# blitzbox.net
KiCad netlist of a schematic drawn in EAGLE
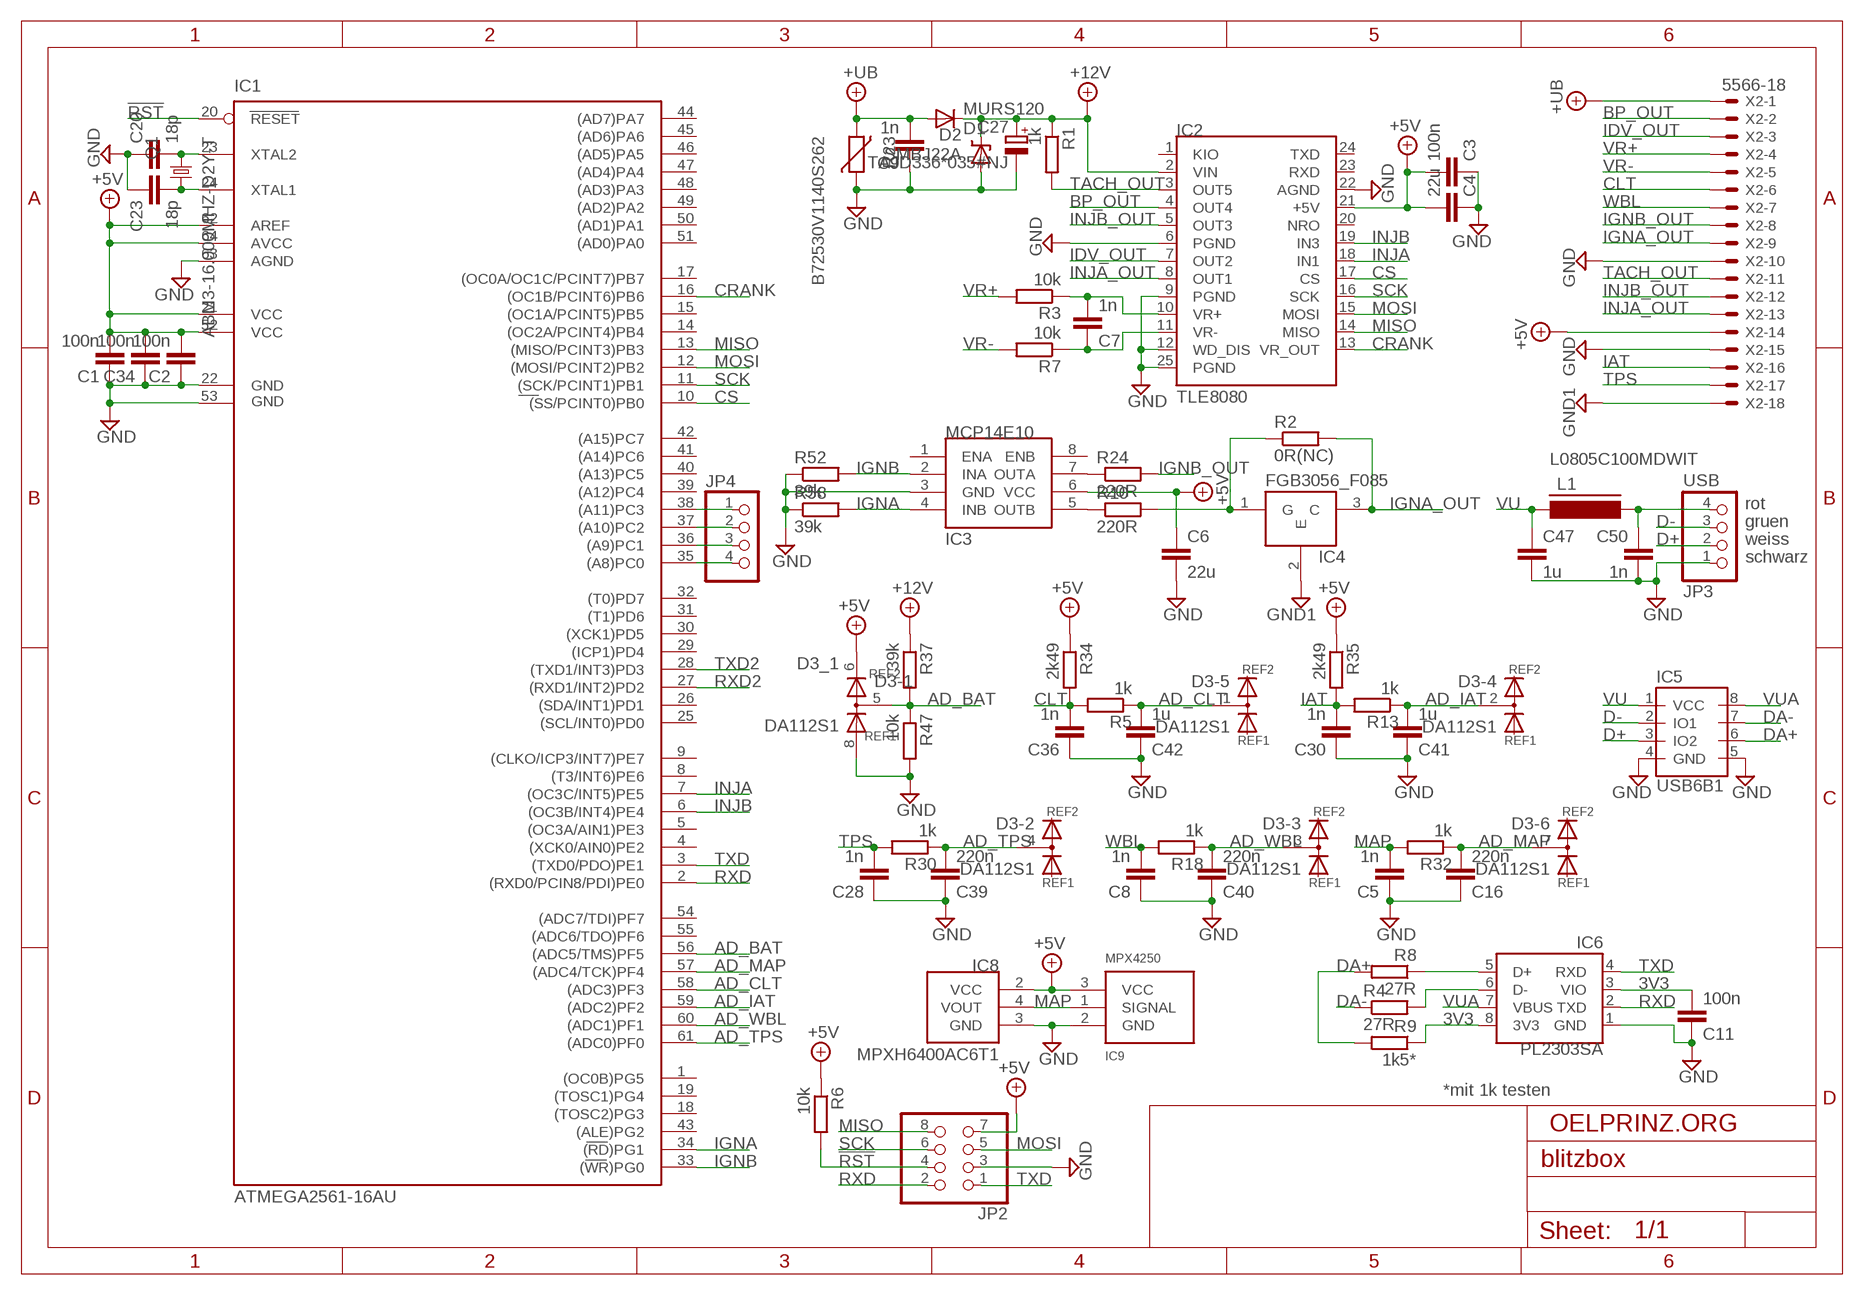
[diagram p0: schematic, sheet 1]

(export (version "E")
  (design (tool "Eeschema 10.0.6"))
  (components
    (comp (ref "C1")
      (value "100n")
      (footprint "eagle-import:C0805")
      (libsource (lib "eagle-import") (part "C-EUC0805"))
    )
    (comp (ref "C2")
      (value "100n")
      (footprint "eagle-import:C0805")
      (libsource (lib "eagle-import") (part "C-EUC0805"))
    )
    (comp (ref "C3")
      (value "100n")
      (footprint "eagle-import:C0805")
      (libsource (lib "eagle-import") (part "C-EUC0805"))
    )
    (comp (ref "C4")
      (value "22u")
      (footprint "eagle-import:C1210")
      (libsource (lib "eagle-import") (part "C-EUC1210"))
    )
    (comp (ref "C5")
      (value "1n")
      (footprint "eagle-import:C0805")
      (libsource (lib "eagle-import") (part "C-EUC0805"))
    )
    (comp (ref "C6")
      (value "22u")
      (footprint "eagle-import:C1206")
      (libsource (lib "eagle-import") (part "C-EUC1206"))
    )
    (comp (ref "C7")
      (value "1n")
      (footprint "eagle-import:C0805")
      (libsource (lib "eagle-import") (part "C-EUC0805"))
    )
    (comp (ref "C8")
      (value "1n")
      (footprint "eagle-import:C0805")
      (libsource (lib "eagle-import") (part "C-EUC0805"))
    )
    (comp (ref "C9")
      (value "1n")
      (footprint "eagle-import:C0805")
      (libsource (lib "eagle-import") (part "C-EUC0805"))
    )
    (comp (ref "C11")
      (value "100n")
      (footprint "eagle-import:C0805")
      (libsource (lib "eagle-import") (part "C-EUC0805"))
    )
    (comp (ref "C16")
      (value "220n")
      (footprint "eagle-import:C0805")
      (libsource (lib "eagle-import") (part "C-EUC0805"))
    )
    (comp (ref "C20")
      (value "18p")
      (footprint "eagle-import:C0805")
      (libsource (lib "eagle-import") (part "C-EUC0805"))
    )
    (comp (ref "C23")
      (value "18p")
      (footprint "eagle-import:C0805")
      (libsource (lib "eagle-import") (part "C-EUC0805"))
    )
    (comp (ref "C27")
      (value "TAJD336*035#NJ")
      (footprint "eagle-import:SMC_D")
      (libsource (lib "eagle-import") (part "CPOL-EUSMCD"))
    )
    (comp (ref "C28")
      (value "1n")
      (footprint "eagle-import:C0805")
      (libsource (lib "eagle-import") (part "C-EUC0805"))
    )
    (comp (ref "C30")
      (value "1n")
      (footprint "eagle-import:C0805")
      (libsource (lib "eagle-import") (part "C-EUC0805"))
    )
    (comp (ref "C34")
      (value "100n")
      (footprint "eagle-import:C0805")
      (libsource (lib "eagle-import") (part "C-EUC0805"))
    )
    (comp (ref "C36")
      (value "1n")
      (footprint "eagle-import:C0805")
      (libsource (lib "eagle-import") (part "C-EUC0805"))
    )
    (comp (ref "C39")
      (value "220n")
      (footprint "eagle-import:C0805")
      (libsource (lib "eagle-import") (part "C-EUC0805"))
    )
    (comp (ref "C40")
      (value "220n")
      (footprint "eagle-import:C0805")
      (libsource (lib "eagle-import") (part "C-EUC0805"))
    )
    (comp (ref "C41")
      (value "1u")
      (footprint "eagle-import:C0805")
      (libsource (lib "eagle-import") (part "C-EUC0805"))
    )
    (comp (ref "C42")
      (value "1u")
      (footprint "eagle-import:C0805")
      (libsource (lib "eagle-import") (part "C-EUC0805"))
    )
    (comp (ref "C47")
      (value "1u")
      (footprint "eagle-import:C0805")
      (libsource (lib "eagle-import") (part "C-EUC0805"))
    )
    (comp (ref "C50")
      (value "1n")
      (footprint "eagle-import:C0805")
      (libsource (lib "eagle-import") (part "C-EUC0805"))
    )
    (comp (ref "D1")
      (value "MURS120")
      (footprint "eagle-import:MURS120")
      (libsource (lib "eagle-import") (part "MURS120"))
    )
    (comp (ref "D2")
      (value "SMBJ22A")
      (footprint "eagle-import:SMBJ")
      (libsource (lib "eagle-import") (part "SUPPRESSOR-SMBJ"))
    )
    (comp (ref "D3")
      (value "DA112S1")
      (footprint "eagle-import:SO08")
      (fields (field (name "MF") "Arrow Electronics"))
      (libsource (lib "eagle-import") (part "DA112S1"))
    )
    (comp (ref "IC1")
      (value "ATMEGA2561-16AU")
      (footprint "eagle-import:TQFP64")
      (libsource (lib "eagle-import") (part "ATMEGA2561AU-16"))
    )
    (comp (ref "IC2")
      (value "TLE8080")
      (footprint "eagle-import:TLE8080")
      (libsource (lib "eagle-import") (part "TLE8080"))
    )
    (comp (ref "IC3")
      (value "MCP14E10")
      (footprint "eagle-import:SO-08")
      (libsource (lib "eagle-import") (part "MCP14E10"))
    )
    (comp (ref "IC4")
      (value "FGB3056_F085")
      (footprint "eagle-import:TO263")
      (libsource (lib "eagle-import") (part "FGB3056_F085"))
    )
    (comp (ref "IC5")
      (value "USB6B1")
      (footprint "eagle-import:SO08")
      (libsource (lib "eagle-import") (part "USB6B1"))
    )
    (comp (ref "IC6")
      (value "PL2303SA")
      (footprint "eagle-import:SO-08")
      (libsource (lib "eagle-import") (part "PL2303SA"))
    )
    (comp (ref "IC8")
      (value "MPXH6400AC6T1")
      (footprint "eagle-import:MPXH6400")
      (libsource (lib "eagle-import") (part "MPXH6400"))
    )
    (comp (ref "IC9")
      (value "MPX4250")
      (footprint "eagle-import:MPX4250")
      (libsource (lib "eagle-import") (part "MPX4250"))
    )
    (comp (ref "JP2")
      (value "PINHD-2X4")
      (footprint "eagle-import:2X04")
      (libsource (lib "eagle-import") (part "PINHD-2X4"))
    )
    (comp (ref "JP3")
      (value "USB")
      (footprint "eagle-import:1X04")
      (libsource (lib "eagle-import") (part "PINHD-1X4"))
    )
    (comp (ref "JP4")
      (value "PINHD-1X4")
      (footprint "eagle-import:1X04")
      (libsource (lib "eagle-import") (part "PINHD-1X4"))
    )
    (comp (ref "L1")
      (value "L0805C100MDWIT")
      (footprint "eagle-import:FB805")
      (libsource (lib "eagle-import") (part "FERRITE_BEAD805"))
    )
    (comp (ref "Q1")
      (value "ABM3-16.000MHZ-D2Y-T")
      (footprint "eagle-import:ABM3")
      (libsource (lib "eagle-import") (part "ABM3-8.000MHZ-D2Y-T"))
    )
    (comp (ref "R1")
      (value "1k")
      (footprint "eagle-import:R0805")
      (libsource (lib "eagle-import") (part "R-EU_R0805"))
    )
    (comp (ref "R2")
      (value "0R(NC)")
      (footprint "eagle-import:R0805")
      (libsource (lib "eagle-import") (part "R-EU_R0805"))
    )
    (comp (ref "R3")
      (value "10k")
      (footprint "eagle-import:R0805")
      (libsource (lib "eagle-import") (part "R-EU_R0805"))
    )
    (comp (ref "R4")
      (value "27R")
      (footprint "eagle-import:R0805")
      (libsource (lib "eagle-import") (part "R-EU_R0805"))
    )
    (comp (ref "R5")
      (value "1k")
      (footprint "eagle-import:R0805")
      (libsource (lib "eagle-import") (part "R-EU_R0805"))
    )
    (comp (ref "R6")
      (value "10k")
      (footprint "eagle-import:R0805")
      (libsource (lib "eagle-import") (part "R-EU_R0805"))
    )
    (comp (ref "R7")
      (value "10k")
      (footprint "eagle-import:R0805")
      (libsource (lib "eagle-import") (part "R-EU_R0805"))
    )
    (comp (ref "R8")
      (value "27R")
      (footprint "eagle-import:R0805")
      (libsource (lib "eagle-import") (part "R-EU_R0805"))
    )
    (comp (ref "R9")
      (value "1k5*")
      (footprint "eagle-import:R0805")
      (libsource (lib "eagle-import") (part "R-EU_R0805"))
    )
    (comp (ref "R10")
      (value "220R")
      (footprint "eagle-import:R0805")
      (libsource (lib "eagle-import") (part "R-EU_R0805"))
    )
    (comp (ref "R13")
      (value "1k")
      (footprint "eagle-import:R0805")
      (libsource (lib "eagle-import") (part "R-EU_R0805"))
    )
    (comp (ref "R18")
      (value "1k")
      (footprint "eagle-import:R0805")
      (libsource (lib "eagle-import") (part "R-EU_R0805"))
    )
    (comp (ref "R23")
      (value "B72530V1140S262")
      (footprint "eagle-import:CT_CN1210")
      (libsource (lib "eagle-import") (part "VARISTORCN1210"))
    )
    (comp (ref "R24")
      (value "220R")
      (footprint "eagle-import:R0805")
      (libsource (lib "eagle-import") (part "R-EU_R0805"))
    )
    (comp (ref "R30")
      (value "1k")
      (footprint "eagle-import:R0805")
      (libsource (lib "eagle-import") (part "R-EU_R0805"))
    )
    (comp (ref "R32")
      (value "1k")
      (footprint "eagle-import:R0805")
      (libsource (lib "eagle-import") (part "R-EU_R0805"))
    )
    (comp (ref "R34")
      (value "2k49")
      (footprint "eagle-import:R0805")
      (libsource (lib "eagle-import") (part "R-EU_R0805"))
    )
    (comp (ref "R35")
      (value "2k49")
      (footprint "eagle-import:R0805")
      (libsource (lib "eagle-import") (part "R-EU_R0805"))
    )
    (comp (ref "R37")
      (value "39k")
      (footprint "eagle-import:R0805")
      (libsource (lib "eagle-import") (part "R-EU_R0805"))
    )
    (comp (ref "R47")
      (value "10k")
      (footprint "eagle-import:R0805")
      (libsource (lib "eagle-import") (part "R-EU_R0805"))
    )
    (comp (ref "R52")
      (value "39k")
      (footprint "eagle-import:R0805")
      (libsource (lib "eagle-import") (part "R-EU_R0805"))
    )
    (comp (ref "R58")
      (value "39k")
      (footprint "eagle-import:R0805")
      (libsource (lib "eagle-import") (part "R-EU_R0805"))
    )
    (comp (ref "X2")
      (value "5566-18")
      (footprint "eagle-import:5566-18")
      (libsource (lib "eagle-import") (part "5566-18"))
    )
  )
  (nets
    (net (code "1") (name "+5V") (class "Default")
      (node (ref "C1") (pin "2") (pinfunction "2_2") (pintype "passive"))
      (node (ref "C2") (pin "2") (pinfunction "2_2") (pintype "passive"))
      (node (ref "C3") (pin "2") (pinfunction "2_2") (pintype "passive"))
      (node (ref "C34") (pin "2") (pinfunction "2_2") (pintype "passive"))
      (node (ref "C4") (pin "2") (pinfunction "2_2") (pintype "passive"))
      (node (ref "C6") (pin "1") (pinfunction "1_1") (pintype "passive"))
      (node (ref "D3") (pin "6") (pinfunction "REF2_6") (pintype "passive"))
      (node (ref "IC1") (pin "21") (pinfunction "VCC_21") (pintype "power_in"))
      (node (ref "IC1") (pin "52") (pinfunction "VCC1_52") (pintype "power_in"))
      (node (ref "IC1") (pin "62") (pinfunction "AREF_62") (pintype "bidirectional"))
      (node (ref "IC1") (pin "64") (pinfunction "AVCC_64") (pintype "power_in"))
      (node (ref "IC2") (pin "21") (pinfunction "+5V_21") (pintype "bidirectional"))
      (node (ref "IC3") (pin "6") (pinfunction "VCC_6") (pintype "bidirectional"))
      (node (ref "IC8") (pin "2") (pinfunction "VCC_2") (pintype "bidirectional"))
      (node (ref "IC9") (pin "3") (pinfunction "VCC_3") (pintype "bidirectional"))
      (node (ref "JP2") (pin "7") (pinfunction "7_7") (pintype "passive"))
      (node (ref "R34") (pin "1") (pinfunction "1_1") (pintype "passive"))
      (node (ref "R35") (pin "1") (pinfunction "1_1") (pintype "passive"))
      (node (ref "R6") (pin "1") (pinfunction "1_1") (pintype "passive"))
      (node (ref "X2") (pin "14") (pinfunction "S_14") (pintype "passive"))
    )
    (net (code "2") (name "+12V") (class "Default")
      (node (ref "C27") (pin "+") (pinfunction "+_+") (pintype "passive"))
      (node (ref "D1") (pin "2") (pinfunction "C_2") (pintype "passive"))
      (node (ref "D2") (pin "C") (pinfunction "C_C") (pintype "passive"))
      (node (ref "IC2") (pin "2") (pinfunction "VIN_2") (pintype "bidirectional"))
      (node (ref "R1") (pin "1") (pinfunction "1_1") (pintype "passive"))
      (node (ref "R37") (pin "1") (pinfunction "1_1") (pintype "passive"))
    )
    (net (code "3") (name "+UB") (class "Default")
      (node (ref "C9") (pin "2") (pinfunction "2_2") (pintype "passive"))
      (node (ref "D1") (pin "1") (pinfunction "A_1") (pintype "passive"))
      (node (ref "R23") (pin "2") (pinfunction "2_2") (pintype "passive"))
      (node (ref "X2") (pin "1") (pinfunction "S_1") (pintype "passive"))
    )
    (net (code "4") (name "/3V3") (class "Default")
      (node (ref "C11") (pin "2") (pinfunction "2_2") (pintype "passive"))
      (node (ref "IC6") (pin "3") (pinfunction "VIO_3") (pintype "bidirectional"))
      (node (ref "IC6") (pin "8") (pinfunction "3V3_8") (pintype "bidirectional"))
      (node (ref "R9") (pin "1") (pinfunction "1_1") (pintype "passive"))
    )
    (net (code "5") (name "/AD_BAT") (class "Default")
      (node (ref "D3") (pin "5") (pinfunction "K_5") (pintype "passive"))
      (node (ref "IC1") (pin "56") (pinfunction "(ADC5/TMS)PF5_56") (pintype "bidirectional"))
      (node (ref "R37") (pin "2") (pinfunction "2_2") (pintype "passive"))
      (node (ref "R47") (pin "1") (pinfunction "1_1") (pintype "passive"))
    )
    (net (code "6") (name "/AD_CLT") (class "Default")
      (node (ref "C42") (pin "2") (pinfunction "2_2") (pintype "passive"))
      (node (ref "D3") (pin "1") (pinfunction "K_1") (pintype "passive"))
      (node (ref "IC1") (pin "58") (pinfunction "(ADC3)PF3_58") (pintype "bidirectional"))
      (node (ref "R5") (pin "1") (pinfunction "1_1") (pintype "passive"))
    )
    (net (code "7") (name "/AD_IAT") (class "Default")
      (node (ref "C41") (pin "2") (pinfunction "2_2") (pintype "passive"))
      (node (ref "D3") (pin "2") (pinfunction "K_2") (pintype "passive"))
      (node (ref "IC1") (pin "59") (pinfunction "(ADC2)PF2_59") (pintype "bidirectional"))
      (node (ref "R13") (pin "1") (pinfunction "1_1") (pintype "passive"))
    )
    (net (code "8") (name "/AD_MAP") (class "Default")
      (node (ref "C16") (pin "2") (pinfunction "2_2") (pintype "passive"))
      (node (ref "D3") (pin "7") (pinfunction "K_7") (pintype "passive"))
      (node (ref "IC1") (pin "57") (pinfunction "(ADC4/TCK)PF4_57") (pintype "bidirectional"))
      (node (ref "R32") (pin "1") (pinfunction "1_1") (pintype "passive"))
    )
    (net (code "9") (name "/AD_TPS") (class "Default")
      (node (ref "C39") (pin "2") (pinfunction "2_2") (pintype "passive"))
      (node (ref "D3") (pin "4") (pinfunction "K_4") (pintype "passive"))
      (node (ref "IC1") (pin "61") (pinfunction "(ADC0)PF0_61") (pintype "bidirectional"))
      (node (ref "R30") (pin "1") (pinfunction "1_1") (pintype "passive"))
    )
    (net (code "10") (name "/AD_WBL") (class "Default")
      (node (ref "C40") (pin "2") (pinfunction "2_2") (pintype "passive"))
      (node (ref "D3") (pin "3") (pinfunction "K_3") (pintype "passive"))
      (node (ref "IC1") (pin "60") (pinfunction "(ADC1)PF1_60") (pintype "bidirectional"))
      (node (ref "R18") (pin "1") (pinfunction "1_1") (pintype "passive"))
    )
    (net (code "11") (name "/BP_OUT") (class "Default")
      (node (ref "IC2") (pin "4") (pinfunction "OUT4_4") (pintype "bidirectional"))
      (node (ref "X2") (pin "2") (pinfunction "S_2") (pintype "passive"))
    )
    (net (code "12") (name "/CLT") (class "Default")
      (node (ref "C36") (pin "2") (pinfunction "2_2") (pintype "passive"))
      (node (ref "R34") (pin "2") (pinfunction "2_2") (pintype "passive"))
      (node (ref "R5") (pin "2") (pinfunction "2_2") (pintype "passive"))
      (node (ref "X2") (pin "6") (pinfunction "S_6") (pintype "passive"))
    )
    (net (code "13") (name "/CRANK") (class "Default")
      (node (ref "IC1") (pin "16") (pinfunction "(OC1B/PCINT6)PB6_16") (pintype "bidirectional"))
      (node (ref "IC2") (pin "13") (pinfunction "VR_OUT_13") (pintype "bidirectional"))
    )
    (net (code "14") (name "/CS") (class "Default")
      (node (ref "IC1") (pin "10") (pinfunction "(SS/PCINT0)PB0_10") (pintype "bidirectional"))
      (node (ref "IC2") (pin "17") (pinfunction "CS_17") (pintype "bidirectional"))
    )
    (net (code "15") (name "/D+") (class "Default")
      (node (ref "IC5") (pin "3") (pinfunction "IO2_3") (pintype "bidirectional"))
      (node (ref "JP3") (pin "2") (pinfunction "2_2") (pintype "passive"))
    )
    (net (code "16") (name "/D-") (class "Default")
      (node (ref "IC5") (pin "2") (pinfunction "IO1_2") (pintype "bidirectional"))
      (node (ref "JP3") (pin "3") (pinfunction "3_3") (pintype "passive"))
    )
    (net (code "17") (name "/DA+") (class "Default")
      (node (ref "IC5") (pin "6") (pinfunction "IO2_6") (pintype "bidirectional"))
      (node (ref "R8") (pin "2") (pinfunction "2_2") (pintype "passive"))
      (node (ref "R9") (pin "2") (pinfunction "2_2") (pintype "passive"))
    )
    (net (code "18") (name "/DA-") (class "Default")
      (node (ref "IC5") (pin "7") (pinfunction "IO1_7") (pintype "bidirectional"))
      (node (ref "R4") (pin "1") (pinfunction "1_1") (pintype "passive"))
    )
    (net (code "19") (name "/IAT") (class "Default")
      (node (ref "C30") (pin "2") (pinfunction "2_2") (pintype "passive"))
      (node (ref "R13") (pin "2") (pinfunction "2_2") (pintype "passive"))
      (node (ref "R35") (pin "2") (pinfunction "2_2") (pintype "passive"))
      (node (ref "X2") (pin "16") (pinfunction "S_16") (pintype "passive"))
    )
    (net (code "20") (name "/IDV_OUT") (class "Default")
      (node (ref "IC2") (pin "7") (pinfunction "OUT2_7") (pintype "bidirectional"))
      (node (ref "X2") (pin "3") (pinfunction "S_3") (pintype "passive"))
    )
    (net (code "21") (name "/IGNA") (class "Default")
      (node (ref "IC1") (pin "34") (pinfunction "(RD)PG1_34") (pintype "bidirectional"))
      (node (ref "IC3") (pin "4") (pinfunction "INB_4") (pintype "bidirectional"))
      (node (ref "R58") (pin "2") (pinfunction "2_2") (pintype "passive"))
    )
    (net (code "22") (name "/IGNA_OUT") (class "Default")
      (node (ref "IC4") (pin "3") (pinfunction "C_3") (pintype "bidirectional"))
      (node (ref "R2") (pin "2") (pinfunction "2_2") (pintype "passive"))
      (node (ref "X2") (pin "9") (pinfunction "S_9") (pintype "passive"))
    )
    (net (code "23") (name "/IGNB") (class "Default")
      (node (ref "IC1") (pin "33") (pinfunction "(WR)PG0_33") (pintype "bidirectional"))
      (node (ref "IC3") (pin "2") (pinfunction "INA_2") (pintype "bidirectional"))
      (node (ref "R52") (pin "2") (pinfunction "2_2") (pintype "passive"))
    )
    (net (code "24") (name "/IGNB_OUT") (class "Default")
      (node (ref "R24") (pin "2") (pinfunction "2_2") (pintype "passive"))
      (node (ref "X2") (pin "8") (pinfunction "S_8") (pintype "passive"))
    )
    (net (code "25") (name "/INJA") (class "Default")
      (node (ref "IC1") (pin "7") (pinfunction "(OC3C/INT5)PE5_7") (pintype "bidirectional"))
      (node (ref "IC2") (pin "18") (pinfunction "IN1_18") (pintype "bidirectional"))
    )
    (net (code "26") (name "/INJA_OUT") (class "Default")
      (node (ref "IC2") (pin "8") (pinfunction "OUT1_8") (pintype "bidirectional"))
      (node (ref "X2") (pin "13") (pinfunction "S_13") (pintype "passive"))
    )
    (net (code "27") (name "/INJB") (class "Default")
      (node (ref "IC1") (pin "6") (pinfunction "(OC3B/INT4)PE4_6") (pintype "bidirectional"))
      (node (ref "IC2") (pin "19") (pinfunction "IN3_19") (pintype "bidirectional"))
    )
    (net (code "28") (name "/INJB_OUT") (class "Default")
      (node (ref "IC2") (pin "5") (pinfunction "OUT3_5") (pintype "bidirectional"))
      (node (ref "X2") (pin "12") (pinfunction "S_12") (pintype "passive"))
    )
    (net (code "29") (name "/MAP") (class "Default")
      (node (ref "C5") (pin "2") (pinfunction "2_2") (pintype "passive"))
      (node (ref "IC8") (pin "4") (pinfunction "VOUT_4") (pintype "bidirectional"))
      (node (ref "IC9") (pin "1") (pinfunction "SIGNAL_1") (pintype "bidirectional"))
      (node (ref "R32") (pin "2") (pinfunction "2_2") (pintype "passive"))
    )
    (net (code "30") (name "/MISO") (class "Default")
      (node (ref "IC1") (pin "13") (pinfunction "(MISO/PCINT3)PB3_13") (pintype "bidirectional"))
      (node (ref "IC2") (pin "14") (pinfunction "MISO_14") (pintype "bidirectional"))
      (node (ref "JP2") (pin "8") (pinfunction "8_8") (pintype "passive"))
    )
    (net (code "31") (name "/MOSI") (class "Default")
      (node (ref "IC1") (pin "12") (pinfunction "(MOSI/PCINT2)PB2_12") (pintype "bidirectional"))
      (node (ref "IC2") (pin "15") (pinfunction "MOSI_15") (pintype "bidirectional"))
      (node (ref "JP2") (pin "5") (pinfunction "5_5") (pintype "passive"))
    )
    (net (code "32") (name "/RXD") (class "Default")
      (node (ref "IC1") (pin "2") (pinfunction "(RXD0/PCIN8/PDI)PE0_2") (pintype "bidirectional"))
      (node (ref "IC6") (pin "2") (pinfunction "TXD_2") (pintype "bidirectional"))
      (node (ref "JP2") (pin "2") (pinfunction "2_2") (pintype "passive"))
    )
    (net (code "33") (name "/RXD2") (class "Default")
      (node (ref "IC1") (pin "27") (pinfunction "(RXD1/INT2)PD2_27") (pintype "bidirectional"))
    )
    (net (code "34") (name "/SCK") (class "Default")
      (node (ref "IC1") (pin "11") (pinfunction "(SCK/PCINT1)PB1_11") (pintype "bidirectional"))
      (node (ref "IC2") (pin "16") (pinfunction "SCK_16") (pintype "bidirectional"))
      (node (ref "JP2") (pin "6") (pinfunction "6_6") (pintype "passive"))
    )
    (net (code "35") (name "/TACH_OUT") (class "Default")
      (node (ref "IC2") (pin "3") (pinfunction "OUT5_3") (pintype "bidirectional"))
      (node (ref "R1") (pin "2") (pinfunction "2_2") (pintype "passive"))
      (node (ref "X2") (pin "11") (pinfunction "S_11") (pintype "passive"))
    )
    (net (code "36") (name "/TPS") (class "Default")
      (node (ref "C28") (pin "2") (pinfunction "2_2") (pintype "passive"))
      (node (ref "R30") (pin "2") (pinfunction "2_2") (pintype "passive"))
      (node (ref "X2") (pin "17") (pinfunction "S_17") (pintype "passive"))
    )
    (net (code "37") (name "/TXD") (class "Default")
      (node (ref "IC1") (pin "3") (pinfunction "(TXD0/PDO)PE1_3") (pintype "bidirectional"))
      (node (ref "IC6") (pin "4") (pinfunction "RXD_4") (pintype "bidirectional"))
      (node (ref "JP2") (pin "1") (pinfunction "1_1") (pintype "passive"))
    )
    (net (code "38") (name "/TXD2") (class "Default")
      (node (ref "IC1") (pin "28") (pinfunction "(TXD1/INT3)PD3_28") (pintype "bidirectional"))
    )
    (net (code "39") (name "/VR+") (class "Default")
      (node (ref "R3") (pin "2") (pinfunction "2_2") (pintype "passive"))
      (node (ref "X2") (pin "4") (pinfunction "S_4") (pintype "passive"))
    )
    (net (code "40") (name "/VR-") (class "Default")
      (node (ref "R7") (pin "2") (pinfunction "2_2") (pintype "passive"))
      (node (ref "X2") (pin "5") (pinfunction "S_5") (pintype "passive"))
    )
    (net (code "41") (name "/VU") (class "Default")
      (node (ref "C47") (pin "1") (pinfunction "1_1") (pintype "passive"))
      (node (ref "IC5") (pin "1") (pinfunction "VCC_1") (pintype "power_in"))
      (node (ref "L1") (pin "1") (pinfunction "1_1") (pintype "passive"))
    )
    (net (code "42") (name "/VUA") (class "Default")
      (node (ref "IC5") (pin "8") (pinfunction "VCC_8") (pintype "power_in"))
      (node (ref "IC6") (pin "7") (pinfunction "VBUS_7") (pintype "bidirectional"))
    )
    (net (code "43") (name "/WBL") (class "Default")
      (node (ref "C8") (pin "2") (pinfunction "2_2") (pintype "passive"))
      (node (ref "R18") (pin "2") (pinfunction "2_2") (pintype "passive"))
      (node (ref "X2") (pin "7") (pinfunction "S_7") (pintype "passive"))
    )
    (net (code "44") (name "/~{RST}") (class "Default")
      (node (ref "IC1") (pin "20") (pinfunction "RESET_20") (pintype "input"))
      (node (ref "JP2") (pin "4") (pinfunction "4_4") (pintype "passive"))
      (node (ref "R6") (pin "2") (pinfunction "2_2") (pintype "passive"))
    )
    (net (code "45") (name "GND") (class "Default")
      (node (ref "C1") (pin "1") (pinfunction "1_1") (pintype "passive"))
      (node (ref "C11") (pin "1") (pinfunction "1_1") (pintype "passive"))
      (node (ref "C16") (pin "1") (pinfunction "1_1") (pintype "passive"))
      (node (ref "C2") (pin "1") (pinfunction "1_1") (pintype "passive"))
      (node (ref "C20") (pin "1") (pinfunction "1_1") (pintype "passive"))
      (node (ref "C23") (pin "1") (pinfunction "1_1") (pintype "passive"))
      (node (ref "C27") (pin "-") (pinfunction "-_-") (pintype "passive"))
      (node (ref "C28") (pin "1") (pinfunction "1_1") (pintype "passive"))
      (node (ref "C3") (pin "1") (pinfunction "1_1") (pintype "passive"))
      (node (ref "C30") (pin "1") (pinfunction "1_1") (pintype "passive"))
      (node (ref "C34") (pin "1") (pinfunction "1_1") (pintype "passive"))
      (node (ref "C36") (pin "1") (pinfunction "1_1") (pintype "passive"))
      (node (ref "C39") (pin "1") (pinfunction "1_1") (pintype "passive"))
      (node (ref "C4") (pin "1") (pinfunction "1_1") (pintype "passive"))
      (node (ref "C40") (pin "1") (pinfunction "1_1") (pintype "passive"))
      (node (ref "C41") (pin "1") (pinfunction "1_1") (pintype "passive"))
      (node (ref "C42") (pin "1") (pinfunction "1_1") (pintype "passive"))
      (node (ref "C47") (pin "2") (pinfunction "2_2") (pintype "passive"))
      (node (ref "C5") (pin "1") (pinfunction "1_1") (pintype "passive"))
      (node (ref "C50") (pin "2") (pinfunction "2_2") (pintype "passive"))
      (node (ref "C6") (pin "2") (pinfunction "2_2") (pintype "passive"))
      (node (ref "C8") (pin "1") (pinfunction "1_1") (pintype "passive"))
      (node (ref "C9") (pin "1") (pinfunction "1_1") (pintype "passive"))
      (node (ref "D2") (pin "A") (pinfunction "A_A") (pintype "passive"))
      (node (ref "D3") (pin "8") (pinfunction "REF1_8") (pintype "passive"))
      (node (ref "IC1") (pin "22") (pinfunction "GND_22") (pintype "power_in"))
      (node (ref "IC1") (pin "53") (pinfunction "GND1_53") (pintype "power_in"))
      (node (ref "IC1") (pin "63") (pinfunction "AGND_63") (pintype "power_in"))
      (node (ref "IC2") (pin "12") (pinfunction "WD_DIS_12") (pintype "bidirectional"))
      (node (ref "IC2") (pin "22") (pinfunction "AGND_22") (pintype "bidirectional"))
      (node (ref "IC2") (pin "25") (pinfunction "PGND_25") (pintype "bidirectional"))
      (node (ref "IC2") (pin "6") (pinfunction "PGND_6") (pintype "bidirectional"))
      (node (ref "IC2") (pin "9") (pinfunction "PGND_9") (pintype "bidirectional"))
      (node (ref "IC3") (pin "3") (pinfunction "GND_3") (pintype "bidirectional"))
      (node (ref "IC5") (pin "4") (pinfunction "GND_4") (pintype "power_in"))
      (node (ref "IC5") (pin "5") (pinfunction "GND_5") (pintype "power_in"))
      (node (ref "IC6") (pin "1") (pinfunction "GND_1") (pintype "bidirectional"))
      (node (ref "IC8") (pin "3") (pinfunction "GND_3") (pintype "bidirectional"))
      (node (ref "IC9") (pin "2") (pinfunction "GND_2") (pintype "bidirectional"))
      (node (ref "JP2") (pin "3") (pinfunction "3_3") (pintype "passive"))
      (node (ref "JP3") (pin "1") (pinfunction "1_1") (pintype "passive"))
      (node (ref "R23") (pin "1") (pinfunction "1_1") (pintype "passive"))
      (node (ref "R47") (pin "2") (pinfunction "2_2") (pintype "passive"))
      (node (ref "R52") (pin "1") (pinfunction "1_1") (pintype "passive"))
      (node (ref "R58") (pin "1") (pinfunction "1_1") (pintype "passive"))
      (node (ref "X2") (pin "10") (pinfunction "S_10") (pintype "passive"))
      (node (ref "X2") (pin "15") (pinfunction "S_15") (pintype "passive"))
    )
    (net (code "46") (name "GND1") (class "Default")
      (node (ref "IC4") (pin "2") (pinfunction "E_2") (pintype "bidirectional"))
      (node (ref "X2") (pin "18") (pinfunction "S_18") (pintype "passive"))
    )
    (net (code "47") (name "Net-(C50-Pad1)") (class "Default")
      (node (ref "C50") (pin "1") (pinfunction "1_1") (pintype "passive"))
      (node (ref "JP3") (pin "4") (pinfunction "4_4") (pintype "passive"))
      (node (ref "L1") (pin "2") (pinfunction "2_2") (pintype "passive"))
    )
    (net (code "48") (name "Net-(IC1-(A8)PC0)") (class "Default")
      (node (ref "IC1") (pin "35") (pinfunction "(A8)PC0_35") (pintype "bidirectional"))
      (node (ref "JP4") (pin "4") (pinfunction "4_4") (pintype "passive"))
    )
    (net (code "49") (name "Net-(IC1-(A9)PC1)") (class "Default")
      (node (ref "IC1") (pin "36") (pinfunction "(A9)PC1_36") (pintype "bidirectional"))
      (node (ref "JP4") (pin "3") (pinfunction "3_3") (pintype "passive"))
    )
    (net (code "50") (name "Net-(IC1-(A10)PC2)") (class "Default")
      (node (ref "IC1") (pin "37") (pinfunction "(A10)PC2_37") (pintype "bidirectional"))
      (node (ref "JP4") (pin "2") (pinfunction "2_2") (pintype "passive"))
    )
    (net (code "51") (name "Net-(IC1-(A11)PC3)") (class "Default")
      (node (ref "IC1") (pin "38") (pinfunction "(A11)PC3_38") (pintype "bidirectional"))
      (node (ref "JP4") (pin "1") (pinfunction "1_1") (pintype "passive"))
    )
    (net (code "52") (name "Net-(IC1-XTAL1)") (class "Default")
      (node (ref "C23") (pin "2") (pinfunction "2_2") (pintype "passive"))
      (node (ref "IC1") (pin "24") (pinfunction "XTAL1_24") (pintype "input"))
      (node (ref "Q1") (pin "2") (pinfunction "2_2") (pintype "bidirectional"))
    )
    (net (code "53") (name "Net-(IC1-XTAL2)") (class "Default")
      (node (ref "C20") (pin "2") (pinfunction "2_2") (pintype "passive"))
      (node (ref "IC1") (pin "23") (pinfunction "XTAL2_23") (pintype "output"))
      (node (ref "Q1") (pin "1") (pinfunction "1_1") (pintype "bidirectional"))
    )
    (net (code "54") (name "Net-(IC2-VR+)") (class "Default")
      (node (ref "C7") (pin "2") (pinfunction "2_2") (pintype "passive"))
      (node (ref "IC2") (pin "10") (pinfunction "VR+_10") (pintype "bidirectional"))
      (node (ref "R3") (pin "1") (pinfunction "1_1") (pintype "passive"))
    )
    (net (code "55") (name "Net-(IC2-VR-)") (class "Default")
      (node (ref "C7") (pin "1") (pinfunction "1_1") (pintype "passive"))
      (node (ref "IC2") (pin "11") (pinfunction "VR-_11") (pintype "bidirectional"))
      (node (ref "R7") (pin "1") (pinfunction "1_1") (pintype "passive"))
    )
    (net (code "56") (name "Net-(IC3-OUTA)") (class "Default")
      (node (ref "IC3") (pin "7") (pinfunction "OUTA_7") (pintype "bidirectional"))
      (node (ref "R24") (pin "1") (pinfunction "1_1") (pintype "passive"))
    )
    (net (code "57") (name "Net-(IC3-OUTB)") (class "Default")
      (node (ref "IC3") (pin "5") (pinfunction "OUTB_5") (pintype "bidirectional"))
      (node (ref "R10") (pin "1") (pinfunction "1_1") (pintype "passive"))
    )
    (net (code "58") (name "Net-(IC4-G)") (class "Default")
      (node (ref "IC4") (pin "1") (pinfunction "G_1") (pintype "bidirectional"))
      (node (ref "R10") (pin "2") (pinfunction "2_2") (pintype "passive"))
      (node (ref "R2") (pin "1") (pinfunction "1_1") (pintype "passive"))
    )
    (net (code "59") (name "Net-(IC6-D+)") (class "Default")
      (node (ref "IC6") (pin "5") (pinfunction "D+_5") (pintype "bidirectional"))
      (node (ref "R8") (pin "1") (pinfunction "1_1") (pintype "passive"))
    )
    (net (code "60") (name "Net-(IC6-D-)") (class "Default")
      (node (ref "IC6") (pin "6") (pinfunction "D-_6") (pintype "bidirectional"))
      (node (ref "R4") (pin "2") (pinfunction "2_2") (pintype "passive"))
    )
    (net (code "61") (name "unconnected-(IC1-(A12)PC4-Pad39)") (class "Default")
      (node (ref "IC1") (pin "39") (pinfunction "(A12)PC4_39") (pintype "bidirectional"))
    )
    (net (code "62") (name "unconnected-(IC1-(A13)PC5-Pad40)") (class "Default")
      (node (ref "IC1") (pin "40") (pinfunction "(A13)PC5_40") (pintype "bidirectional"))
    )
    (net (code "63") (name "unconnected-(IC1-(A14)PC6-Pad41)") (class "Default")
      (node (ref "IC1") (pin "41") (pinfunction "(A14)PC6_41") (pintype "bidirectional"))
    )
    (net (code "64") (name "unconnected-(IC1-(A15)PC7-Pad42)") (class "Default")
      (node (ref "IC1") (pin "42") (pinfunction "(A15)PC7_42") (pintype "bidirectional"))
    )
    (net (code "65") (name "unconnected-(IC1-(AD0)PA0-Pad51)") (class "Default")
      (node (ref "IC1") (pin "51") (pinfunction "(AD0)PA0_51") (pintype "bidirectional"))
    )
    (net (code "66") (name "unconnected-(IC1-(AD1)PA1-Pad50)") (class "Default")
      (node (ref "IC1") (pin "50") (pinfunction "(AD1)PA1_50") (pintype "bidirectional"))
    )
    (net (code "67") (name "unconnected-(IC1-(AD2)PA2-Pad49)") (class "Default")
      (node (ref "IC1") (pin "49") (pinfunction "(AD2)PA2_49") (pintype "bidirectional"))
    )
    (net (code "68") (name "unconnected-(IC1-(AD3)PA3-Pad48)") (class "Default")
      (node (ref "IC1") (pin "48") (pinfunction "(AD3)PA3_48") (pintype "bidirectional"))
    )
    (net (code "69") (name "unconnected-(IC1-(AD4)PA4-Pad47)") (class "Default")
      (node (ref "IC1") (pin "47") (pinfunction "(AD4)PA4_47") (pintype "bidirectional"))
    )
    (net (code "70") (name "unconnected-(IC1-(AD5)PA5-Pad46)") (class "Default")
      (node (ref "IC1") (pin "46") (pinfunction "(AD5)PA5_46") (pintype "bidirectional"))
    )
    (net (code "71") (name "unconnected-(IC1-(AD6)PA6-Pad45)") (class "Default")
      (node (ref "IC1") (pin "45") (pinfunction "(AD6)PA6_45") (pintype "bidirectional"))
    )
    (net (code "72") (name "unconnected-(IC1-(AD7)PA7-Pad44)") (class "Default")
      (node (ref "IC1") (pin "44") (pinfunction "(AD7)PA7_44") (pintype "bidirectional"))
    )
    (net (code "73") (name "unconnected-(IC1-(ADC6{slash}TDO)PF6-Pad55)") (class "Default")
      (node (ref "IC1") (pin "55") (pinfunction "(ADC6/TDO)PF6_55") (pintype "bidirectional"))
    )
    (net (code "74") (name "unconnected-(IC1-(ADC7{slash}TDI)PF7-Pad54)") (class "Default")
      (node (ref "IC1") (pin "54") (pinfunction "(ADC7/TDI)PF7_54") (pintype "bidirectional"))
    )
    (net (code "75") (name "unconnected-(IC1-(ALE)PG2-Pad43)") (class "Default")
      (node (ref "IC1") (pin "43") (pinfunction "(ALE)PG2_43") (pintype "bidirectional"))
    )
    (net (code "76") (name "unconnected-(IC1-(CLKO{slash}ICP3{slash}INT7)PE7-Pad9)") (class "Default")
      (node (ref "IC1") (pin "9") (pinfunction "(CLKO/ICP3/INT7)PE7_9") (pintype "bidirectional"))
    )
    (net (code "77") (name "unconnected-(IC1-(ICP1)PD4-Pad29)") (class "Default")
      (node (ref "IC1") (pin "29") (pinfunction "(ICP1)PD4_29") (pintype "bidirectional"))
    )
    (net (code "78") (name "unconnected-(IC1-(OC0A{slash}OC1C{slash}PCINT7)PB7-Pad17)") (class "Default")
      (node (ref "IC1") (pin "17") (pinfunction "(OC0A/OC1C/PCINT7)PB7_17") (pintype "bidirectional"))
    )
    (net (code "79") (name "unconnected-(IC1-(OC0B)PG5-Pad1)") (class "Default")
      (node (ref "IC1") (pin "1") (pinfunction "(OC0B)PG5_1") (pintype "bidirectional"))
    )
    (net (code "80") (name "unconnected-(IC1-(OC1A{slash}PCINT5)PB5-Pad15)") (class "Default")
      (node (ref "IC1") (pin "15") (pinfunction "(OC1A/PCINT5)PB5_15") (pintype "bidirectional"))
    )
    (net (code "81") (name "unconnected-(IC1-(OC2A{slash}PCINT4)PB4-Pad14)") (class "Default")
      (node (ref "IC1") (pin "14") (pinfunction "(OC2A/PCINT4)PB4_14") (pintype "bidirectional"))
    )
    (net (code "82") (name "unconnected-(IC1-(OC3A{slash}AIN1)PE3-Pad5)") (class "Default")
      (node (ref "IC1") (pin "5") (pinfunction "(OC3A/AIN1)PE3_5") (pintype "bidirectional"))
    )
    (net (code "83") (name "unconnected-(IC1-(SCL{slash}INT0)PD0-Pad25)") (class "Default")
      (node (ref "IC1") (pin "25") (pinfunction "(SCL/INT0)PD0_25") (pintype "bidirectional"))
    )
    (net (code "84") (name "unconnected-(IC1-(SDA{slash}INT1)PD1-Pad26)") (class "Default")
      (node (ref "IC1") (pin "26") (pinfunction "(SDA/INT1)PD1_26") (pintype "bidirectional"))
    )
    (net (code "85") (name "unconnected-(IC1-(T0)PD7-Pad32)") (class "Default")
      (node (ref "IC1") (pin "32") (pinfunction "(T0)PD7_32") (pintype "bidirectional"))
    )
    (net (code "86") (name "unconnected-(IC1-(T1)PD6-Pad31)") (class "Default")
      (node (ref "IC1") (pin "31") (pinfunction "(T1)PD6_31") (pintype "bidirectional"))
    )
    (net (code "87") (name "unconnected-(IC1-(T3{slash}INT6)PE6-Pad8)") (class "Default")
      (node (ref "IC1") (pin "8") (pinfunction "(T3/INT6)PE6_8") (pintype "bidirectional"))
    )
    (net (code "88") (name "unconnected-(IC1-(TOSC1)PG4-Pad19)") (class "Default")
      (node (ref "IC1") (pin "19") (pinfunction "(TOSC1)PG4_19") (pintype "bidirectional"))
    )
    (net (code "89") (name "unconnected-(IC1-(TOSC2)PG3-Pad18)") (class "Default")
      (node (ref "IC1") (pin "18") (pinfunction "(TOSC2)PG3_18") (pintype "bidirectional"))
    )
    (net (code "90") (name "unconnected-(IC1-(XCK0{slash}AIN0)PE2-Pad4)") (class "Default")
      (node (ref "IC1") (pin "4") (pinfunction "(XCK0/AIN0)PE2_4") (pintype "bidirectional"))
    )
    (net (code "91") (name "unconnected-(IC1-(XCK1)PD5-Pad30)") (class "Default")
      (node (ref "IC1") (pin "30") (pinfunction "(XCK1)PD5_30") (pintype "bidirectional"))
    )
    (net (code "92") (name "unconnected-(IC2-KIO-Pad1)") (class "Default")
      (node (ref "IC2") (pin "1") (pinfunction "KIO_1") (pintype "bidirectional"))
    )
    (net (code "93") (name "unconnected-(IC2-NRO-Pad20)") (class "Default")
      (node (ref "IC2") (pin "20") (pinfunction "NRO_20") (pintype "bidirectional"))
    )
    (net (code "94") (name "unconnected-(IC2-RXD-Pad23)") (class "Default")
      (node (ref "IC2") (pin "23") (pinfunction "RXD_23") (pintype "bidirectional"))
    )
    (net (code "95") (name "unconnected-(IC2-TXD-Pad24)") (class "Default")
      (node (ref "IC2") (pin "24") (pinfunction "TXD_24") (pintype "bidirectional"))
    )
    (net (code "96") (name "unconnected-(IC3-ENA-Pad1)") (class "Default")
      (node (ref "IC3") (pin "1") (pinfunction "ENA_1") (pintype "bidirectional"))
    )
    (net (code "97") (name "unconnected-(IC3-ENB-Pad8)") (class "Default")
      (node (ref "IC3") (pin "8") (pinfunction "ENB_8") (pintype "bidirectional"))
    )
  )
)
